# QSPI_FLASH.net
KiCad netlist of a schematic drawn in Altium Designer
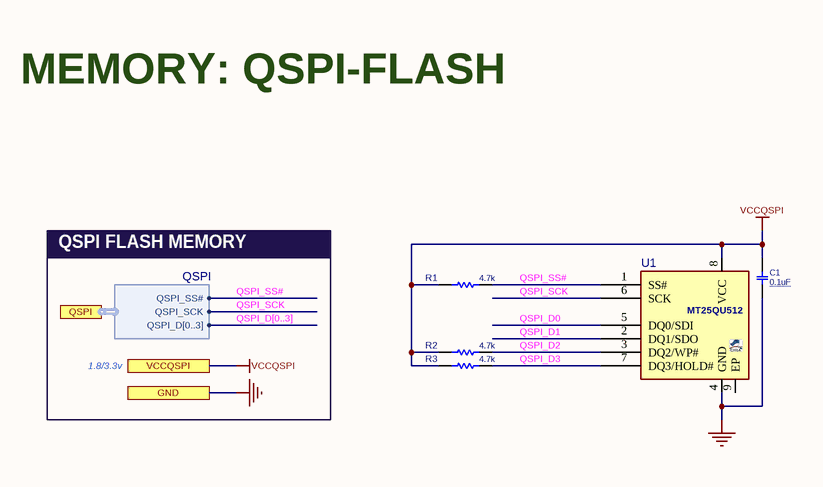
[diagram p0: QSPI_FLASH.SchDoc]

(export (version "E")
  (design (tool "Eeschema 10.0.6"))
  (components
    (comp (ref "C1")
      (value "0.1uF")
      (footprint "C0402")
      (description "CAP, MLCC")
      (fields (field (name "MANF_P#") "MANF_PART#") (field (name "MANF") "Murata"))
      (libsource (lib "passive_smd") (part "CAP_SMD_MLCC"))
    )
    (comp (ref "R1")
      (value "4.7k")
      (footprint "R0402")
      (description "RESISTOR, SMD")
      (libsource (lib "passive_smd") (part "RES_SMD"))
    )
    (comp (ref "R2")
      (value "4.7k")
      (footprint "R0402")
      (description "RESISTOR, SMD")
      (libsource (lib "passive_smd") (part "RES_SMD"))
    )
    (comp (ref "R3")
      (value "4.7k")
      (footprint "R0402")
      (description "RESISTOR, SMD")
      (libsource (lib "passive_smd") (part "RES_SMD"))
    )
    (comp (ref "U1")
      (value "MT25QU512")
      (footprint "SON127_8T_6080")
      (description "SPI FLASH Memory, 512Mb (128M x4), 108MHz")
      (fields (field (name "MANF") "Micron") (field (name "MANF_P#") "MT25QU512ABB1EW9"))
      (libsource (lib "memory_flash_spi") (part "N25Q512_SON8"))
    )
  )
  (nets
    (net (code "2") (name "/QSPI_D0") (class "Default")
      (node (ref "U1") (pin "5") (pinfunction "DQ0/SDI_5") (pintype "passive"))
    )
    (net (code "3") (name "/QSPI_D1") (class "Default")
      (node (ref "U1") (pin "2") (pinfunction "DQ1/SDO_2") (pintype "passive"))
    )
    (net (code "4") (name "/QSPI_D2") (class "Default")
      (node (ref "R2") (pin "2") (pinfunction "2_2") (pintype "passive"))
      (node (ref "U1") (pin "3") (pinfunction "DQ2/WP#_3") (pintype "passive"))
    )
    (net (code "5") (name "/QSPI_D3") (class "Default")
      (node (ref "R3") (pin "2") (pinfunction "2_2") (pintype "passive"))
      (node (ref "U1") (pin "7") (pinfunction "DQ3/HOLD#_7") (pintype "passive"))
    )
    (net (code "6") (name "/QSPI_SCK") (class "Default")
      (node (ref "U1") (pin "6") (pinfunction "SCK_6") (pintype "passive"))
    )
    (net (code "7") (name "/QSPI_SS#") (class "Default")
      (node (ref "R1") (pin "2") (pinfunction "2_2") (pintype "passive"))
      (node (ref "U1") (pin "1") (pinfunction "SS#_1") (pintype "passive"))
    )
    (net (code "10") (name "GND") (class "Default")
      (node (ref "C1") (pin "2") (pinfunction "2_2") (pintype "passive"))
      (node (ref "U1") (pin "4") (pinfunction "GND_4") (pintype "passive"))
    )
    (net (code "11") (name "VCCQSPI") (class "Default")
      (node (ref "C1") (pin "1") (pinfunction "1_1") (pintype "passive"))
      (node (ref "R1") (pin "1") (pinfunction "1_1") (pintype "passive"))
      (node (ref "R2") (pin "1") (pinfunction "1_1") (pintype "passive"))
      (node (ref "R3") (pin "1") (pinfunction "1_1") (pintype "passive"))
      (node (ref "U1") (pin "8") (pinfunction "VCC_8") (pintype "passive"))
    )
    (net (code "12") (name "unconnected-(U1-EP-Pad9)") (class "Default")
      (node (ref "U1") (pin "9") (pinfunction "EP_9") (pintype "passive"))
    )
  )
)
